# INTRO_Robot_Shield.net
KiCad netlist of a schematic drawn in EAGLE
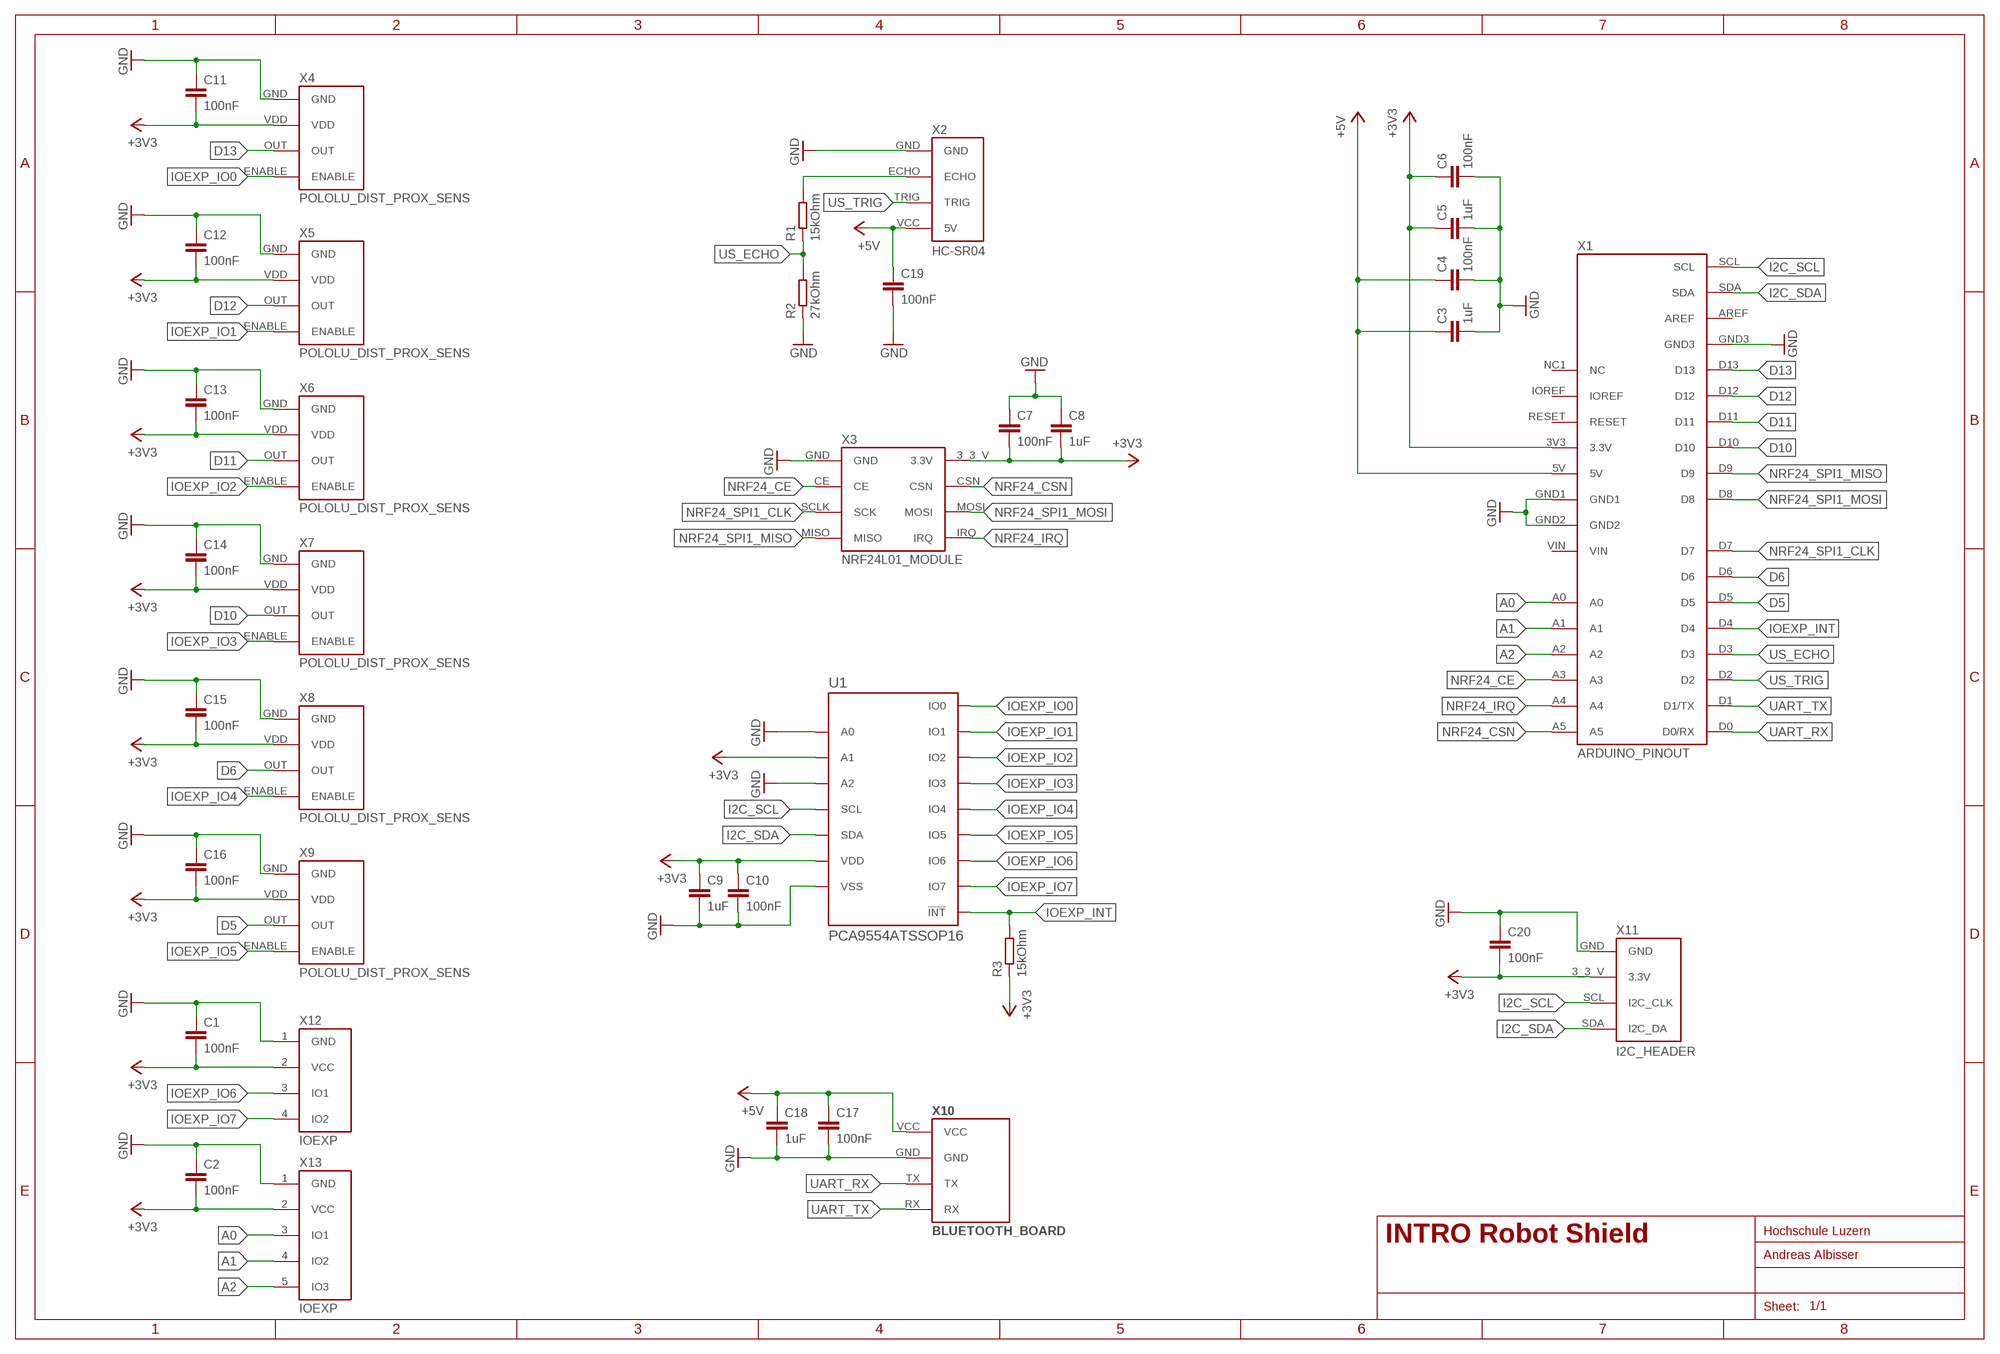
[diagram p0: schematic, sheet 1]

(export (version "E")
  (design (tool "Eeschema 10.0.6"))
  (components
    (comp (ref "C1")
      (value "100nF")
      (footprint "eagle-import:0805")
      (libsource (lib "eagle-import") (part "CAPACITOR0805"))
    )
    (comp (ref "C2")
      (value "100nF")
      (footprint "eagle-import:0805")
      (libsource (lib "eagle-import") (part "CAPACITOR0805"))
    )
    (comp (ref "C3")
      (value "1uF")
      (footprint "eagle-import:0805")
      (libsource (lib "eagle-import") (part "CAPACITOR0805"))
    )
    (comp (ref "C4")
      (value "100nF")
      (footprint "eagle-import:0805")
      (libsource (lib "eagle-import") (part "CAPACITOR0805"))
    )
    (comp (ref "C5")
      (value "1uF")
      (footprint "eagle-import:0805")
      (libsource (lib "eagle-import") (part "CAPACITOR0805"))
    )
    (comp (ref "C6")
      (value "100nF")
      (footprint "eagle-import:0805")
      (libsource (lib "eagle-import") (part "CAPACITOR0805"))
    )
    (comp (ref "C7")
      (value "100nF")
      (footprint "eagle-import:0805")
      (libsource (lib "eagle-import") (part "CAPACITOR0805"))
    )
    (comp (ref "C8")
      (value "1uF")
      (footprint "eagle-import:0805")
      (libsource (lib "eagle-import") (part "CAPACITOR0805"))
    )
    (comp (ref "C9")
      (value "1uF")
      (footprint "eagle-import:0805")
      (libsource (lib "eagle-import") (part "CAPACITOR0805"))
    )
    (comp (ref "C10")
      (value "100nF")
      (footprint "eagle-import:0805")
      (libsource (lib "eagle-import") (part "CAPACITOR0805"))
    )
    (comp (ref "C11")
      (value "100nF")
      (footprint "eagle-import:0805")
      (libsource (lib "eagle-import") (part "CAPACITOR0805"))
    )
    (comp (ref "C12")
      (value "100nF")
      (footprint "eagle-import:0805")
      (libsource (lib "eagle-import") (part "CAPACITOR0805"))
    )
    (comp (ref "C13")
      (value "100nF")
      (footprint "eagle-import:0805")
      (libsource (lib "eagle-import") (part "CAPACITOR0805"))
    )
    (comp (ref "C14")
      (value "100nF")
      (footprint "eagle-import:0805")
      (libsource (lib "eagle-import") (part "CAPACITOR0805"))
    )
    (comp (ref "C15")
      (value "100nF")
      (footprint "eagle-import:0805")
      (libsource (lib "eagle-import") (part "CAPACITOR0805"))
    )
    (comp (ref "C16")
      (value "100nF")
      (footprint "eagle-import:0805")
      (libsource (lib "eagle-import") (part "CAPACITOR0805"))
    )
    (comp (ref "C17")
      (value "100nF")
      (footprint "eagle-import:0805")
      (libsource (lib "eagle-import") (part "CAPACITOR0805"))
    )
    (comp (ref "C18")
      (value "1uF")
      (footprint "eagle-import:0805")
      (libsource (lib "eagle-import") (part "CAPACITOR0805"))
    )
    (comp (ref "C19")
      (value "100nF")
      (footprint "eagle-import:0805")
      (libsource (lib "eagle-import") (part "CAPACITOR0805"))
    )
    (comp (ref "C20")
      (value "100nF")
      (footprint "eagle-import:0805")
      (libsource (lib "eagle-import") (part "CAPACITOR0805"))
    )
    (comp (ref "R1")
      (value "15kOhm")
      (footprint "eagle-import:0805")
      (libsource (lib "eagle-import") (part "RESISTOR0805"))
    )
    (comp (ref "R2")
      (value "27kOhm")
      (footprint "eagle-import:0805")
      (libsource (lib "eagle-import") (part "RESISTOR0805"))
    )
    (comp (ref "R3")
      (value "15kOhm")
      (footprint "eagle-import:0805")
      (libsource (lib "eagle-import") (part "RESISTOR0805"))
    )
    (comp (ref "U1")
      (value "PCA9554ATSSOP16")
      (footprint "eagle-import:TSSOP16")
      (libsource (lib "eagle-import") (part "PCA9554ATSSOP16"))
    )
    (comp (ref "X1")
      (value "ARDUINO_PINOUT")
      (footprint "eagle-import:ARDUINO_PINOUT_INNER_LABEL")
      (libsource (lib "eagle-import") (part "ARDUINO_PINOUTINNER_LABEL"))
    )
    (comp (ref "X2")
      (value "HC-SR04")
      (footprint "eagle-import:HC-SR04_FOOTPRINT")
      (libsource (lib "eagle-import") (part "HC-SR04"))
    )
    (comp (ref "X3")
      (value "NRF24L01_MODULE")
      (footprint "eagle-import:NRF24L01_MODULE_FOOTPRINT")
      (libsource (lib "eagle-import") (part "NRF24L01_MODULE"))
    )
    (comp (ref "X4")
      (value "POLOLU_DIST_PROX_SENS")
      (footprint "eagle-import:POLOLU_DIST_PROX_SENS_FOOTPRINT")
      (libsource (lib "eagle-import") (part "POLOLU_DIST_PROX_SENS"))
    )
    (comp (ref "X5")
      (value "POLOLU_DIST_PROX_SENS")
      (footprint "eagle-import:POLOLU_DIST_PROX_SENS_FOOTPRINT")
      (libsource (lib "eagle-import") (part "POLOLU_DIST_PROX_SENS"))
    )
    (comp (ref "X6")
      (value "POLOLU_DIST_PROX_SENS")
      (footprint "eagle-import:POLOLU_DIST_PROX_SENS_FOOTPRINT")
      (libsource (lib "eagle-import") (part "POLOLU_DIST_PROX_SENS"))
    )
    (comp (ref "X7")
      (value "POLOLU_DIST_PROX_SENS")
      (footprint "eagle-import:POLOLU_DIST_PROX_SENS_FOOTPRINT")
      (libsource (lib "eagle-import") (part "POLOLU_DIST_PROX_SENS"))
    )
    (comp (ref "X8")
      (value "POLOLU_DIST_PROX_SENS")
      (footprint "eagle-import:POLOLU_DIST_PROX_SENS_FOOTPRINT")
      (libsource (lib "eagle-import") (part "POLOLU_DIST_PROX_SENS"))
    )
    (comp (ref "X9")
      (value "POLOLU_DIST_PROX_SENS")
      (footprint "eagle-import:POLOLU_DIST_PROX_SENS_FOOTPRINT")
      (libsource (lib "eagle-import") (part "POLOLU_DIST_PROX_SENS"))
    )
    (comp (ref "X10")
      (value "BLUETOOTH_BOARD")
      (footprint "eagle-import:BT_BOARD_FOOTPRINT")
      (libsource (lib "eagle-import") (part "BLUETOOTH_BOARD"))
    )
    (comp (ref "X11")
      (value "I2C_HEADER")
      (footprint "eagle-import:I2C_HEADER_FOOTPRINT")
      (libsource (lib "eagle-import") (part "I2C_HEADER"))
    )
    (comp (ref "X12")
      (value "IOEXP")
      (footprint "eagle-import:CONNECTORS_STIFTLEISTE_1X4_2.54")
      (libsource (lib "eagle-import") (part "IOEXP_2PTHT_2.54MM"))
    )
    (comp (ref "X13")
      (value "IOEXP")
      (footprint "eagle-import:CONNECTORS_STIFTLEISTE_1X5_2.54")
      (libsource (lib "eagle-import") (part "IOEXP_3PTHT_2.54MM"))
    )
  )
  (nets
    (net (code "1") (name "+3V3") (class "Default")
      (node (ref "C1") (pin "2") (pinfunction "2_2") (pintype "passive"))
      (node (ref "C10") (pin "1") (pinfunction "1_1") (pintype "passive"))
      (node (ref "C11") (pin "2") (pinfunction "2_2") (pintype "passive"))
      (node (ref "C12") (pin "2") (pinfunction "2_2") (pintype "passive"))
      (node (ref "C13") (pin "2") (pinfunction "2_2") (pintype "passive"))
      (node (ref "C14") (pin "2") (pinfunction "2_2") (pintype "passive"))
      (node (ref "C15") (pin "2") (pinfunction "2_2") (pintype "passive"))
      (node (ref "C16") (pin "2") (pinfunction "2_2") (pintype "passive"))
      (node (ref "C2") (pin "2") (pinfunction "2_2") (pintype "passive"))
      (node (ref "C20") (pin "2") (pinfunction "2_2") (pintype "passive"))
      (node (ref "C5") (pin "1") (pinfunction "1_1") (pintype "passive"))
      (node (ref "C6") (pin "1") (pinfunction "1_1") (pintype "passive"))
      (node (ref "C7") (pin "2") (pinfunction "2_2") (pintype "passive"))
      (node (ref "C8") (pin "2") (pinfunction "2_2") (pintype "passive"))
      (node (ref "C9") (pin "1") (pinfunction "1_1") (pintype "passive"))
      (node (ref "R3") (pin "1") (pinfunction "1_1") (pintype "passive"))
      (node (ref "U1") (pin "16") (pinfunction "VDD_16") (pintype "bidirectional"))
      (node (ref "U1") (pin "2") (pinfunction "A1_2") (pintype "bidirectional"))
      (node (ref "X1") (pin "3V3") (pinfunction "3.3V_3V3") (pintype "bidirectional"))
      (node (ref "X11") (pin "3_3_V") (pinfunction "3.3V_3_3_V") (pintype "bidirectional"))
      (node (ref "X12") (pin "2") (pinfunction "VCC_2") (pintype "bidirectional"))
      (node (ref "X13") (pin "2") (pinfunction "VCC_2") (pintype "bidirectional"))
      (node (ref "X3") (pin "3_3_V") (pinfunction "3.3V_3_3_V") (pintype "bidirectional"))
      (node (ref "X4") (pin "VDD") (pinfunction "VDD_VDD") (pintype "bidirectional"))
      (node (ref "X5") (pin "VDD") (pinfunction "VDD_VDD") (pintype "bidirectional"))
      (node (ref "X6") (pin "VDD") (pinfunction "VDD_VDD") (pintype "bidirectional"))
      (node (ref "X7") (pin "VDD") (pinfunction "VDD_VDD") (pintype "bidirectional"))
      (node (ref "X8") (pin "VDD") (pinfunction "VDD_VDD") (pintype "bidirectional"))
      (node (ref "X9") (pin "VDD") (pinfunction "VDD_VDD") (pintype "bidirectional"))
    )
    (net (code "2") (name "+5V") (class "Default")
      (node (ref "C17") (pin "1") (pinfunction "1_1") (pintype "passive"))
      (node (ref "C18") (pin "1") (pinfunction "1_1") (pintype "passive"))
      (node (ref "C19") (pin "1") (pinfunction "1_1") (pintype "passive"))
      (node (ref "C3") (pin "1") (pinfunction "1_1") (pintype "passive"))
      (node (ref "C4") (pin "1") (pinfunction "1_1") (pintype "passive"))
      (node (ref "X1") (pin "5V") (pinfunction "5V_5V") (pintype "bidirectional"))
      (node (ref "X10") (pin "VCC") (pinfunction "VCC_VCC") (pintype "bidirectional"))
      (node (ref "X2") (pin "VCC") (pinfunction "5V_VCC") (pintype "bidirectional"))
    )
    (net (code "3") (name "A0") (class "Default")
      (node (ref "X1") (pin "A0") (pinfunction "A0_A0") (pintype "bidirectional"))
      (node (ref "X13") (pin "3") (pinfunction "IO1_3") (pintype "bidirectional"))
    )
    (net (code "4") (name "A1") (class "Default")
      (node (ref "X1") (pin "A1") (pinfunction "A1_A1") (pintype "bidirectional"))
      (node (ref "X13") (pin "4") (pinfunction "IO2_4") (pintype "bidirectional"))
    )
    (net (code "5") (name "A2") (class "Default")
      (node (ref "X1") (pin "A2") (pinfunction "A2_A2") (pintype "bidirectional"))
      (node (ref "X13") (pin "5") (pinfunction "IO3_5") (pintype "bidirectional"))
    )
    (net (code "6") (name "D5") (class "Default")
      (node (ref "X1") (pin "D5") (pinfunction "D5_D5") (pintype "bidirectional"))
      (node (ref "X9") (pin "OUT") (pinfunction "OUT_OUT") (pintype "bidirectional"))
    )
    (net (code "7") (name "D6") (class "Default")
      (node (ref "X1") (pin "D6") (pinfunction "D6_D6") (pintype "bidirectional"))
      (node (ref "X8") (pin "OUT") (pinfunction "OUT_OUT") (pintype "bidirectional"))
    )
    (net (code "8") (name "D10") (class "Default")
      (node (ref "X1") (pin "D10") (pinfunction "D10_D10") (pintype "bidirectional"))
      (node (ref "X7") (pin "OUT") (pinfunction "OUT_OUT") (pintype "bidirectional"))
    )
    (net (code "9") (name "D11") (class "Default")
      (node (ref "X1") (pin "D11") (pinfunction "D11_D11") (pintype "bidirectional"))
      (node (ref "X6") (pin "OUT") (pinfunction "OUT_OUT") (pintype "bidirectional"))
    )
    (net (code "10") (name "D12") (class "Default")
      (node (ref "X1") (pin "D12") (pinfunction "D12_D12") (pintype "bidirectional"))
      (node (ref "X5") (pin "OUT") (pinfunction "OUT_OUT") (pintype "bidirectional"))
    )
    (net (code "11") (name "D13") (class "Default")
      (node (ref "X1") (pin "D13") (pinfunction "D13_D13") (pintype "bidirectional"))
      (node (ref "X4") (pin "OUT") (pinfunction "OUT_OUT") (pintype "bidirectional"))
    )
    (net (code "12") (name "GND") (class "Default")
      (node (ref "C1") (pin "1") (pinfunction "1_1") (pintype "passive"))
      (node (ref "C10") (pin "2") (pinfunction "2_2") (pintype "passive"))
      (node (ref "C11") (pin "1") (pinfunction "1_1") (pintype "passive"))
      (node (ref "C12") (pin "1") (pinfunction "1_1") (pintype "passive"))
      (node (ref "C13") (pin "1") (pinfunction "1_1") (pintype "passive"))
      (node (ref "C14") (pin "1") (pinfunction "1_1") (pintype "passive"))
      (node (ref "C15") (pin "1") (pinfunction "1_1") (pintype "passive"))
      (node (ref "C16") (pin "1") (pinfunction "1_1") (pintype "passive"))
      (node (ref "C17") (pin "2") (pinfunction "2_2") (pintype "passive"))
      (node (ref "C18") (pin "2") (pinfunction "2_2") (pintype "passive"))
      (node (ref "C19") (pin "2") (pinfunction "2_2") (pintype "passive"))
      (node (ref "C2") (pin "1") (pinfunction "1_1") (pintype "passive"))
      (node (ref "C20") (pin "1") (pinfunction "1_1") (pintype "passive"))
      (node (ref "C3") (pin "2") (pinfunction "2_2") (pintype "passive"))
      (node (ref "C4") (pin "2") (pinfunction "2_2") (pintype "passive"))
      (node (ref "C5") (pin "2") (pinfunction "2_2") (pintype "passive"))
      (node (ref "C6") (pin "2") (pinfunction "2_2") (pintype "passive"))
      (node (ref "C7") (pin "1") (pinfunction "1_1") (pintype "passive"))
      (node (ref "C8") (pin "1") (pinfunction "1_1") (pintype "passive"))
      (node (ref "C9") (pin "2") (pinfunction "2_2") (pintype "passive"))
      (node (ref "R2") (pin "1") (pinfunction "1_1") (pintype "passive"))
      (node (ref "U1") (pin "1") (pinfunction "A0_1") (pintype "bidirectional"))
      (node (ref "U1") (pin "3") (pinfunction "A2_3") (pintype "bidirectional"))
      (node (ref "U1") (pin "8") (pinfunction "VSS_8") (pintype "bidirectional"))
      (node (ref "X1") (pin "GND1") (pinfunction "GND1_GND1") (pintype "bidirectional"))
      (node (ref "X1") (pin "GND2") (pinfunction "GND2_GND2") (pintype "bidirectional"))
      (node (ref "X1") (pin "GND3") (pinfunction "GND3_GND3") (pintype "bidirectional"))
      (node (ref "X10") (pin "GND") (pinfunction "GND_GND") (pintype "bidirectional"))
      (node (ref "X11") (pin "GND") (pinfunction "GND_GND") (pintype "bidirectional"))
      (node (ref "X12") (pin "1") (pinfunction "GND_1") (pintype "bidirectional"))
      (node (ref "X13") (pin "1") (pinfunction "GND_1") (pintype "bidirectional"))
      (node (ref "X2") (pin "GND") (pinfunction "GND_GND") (pintype "bidirectional"))
      (node (ref "X3") (pin "GND") (pinfunction "GND_GND") (pintype "bidirectional"))
      (node (ref "X4") (pin "GND") (pinfunction "GND_GND") (pintype "bidirectional"))
      (node (ref "X5") (pin "GND") (pinfunction "GND_GND") (pintype "bidirectional"))
      (node (ref "X6") (pin "GND") (pinfunction "GND_GND") (pintype "bidirectional"))
      (node (ref "X7") (pin "GND") (pinfunction "GND_GND") (pintype "bidirectional"))
      (node (ref "X8") (pin "GND") (pinfunction "GND_GND") (pintype "bidirectional"))
      (node (ref "X9") (pin "GND") (pinfunction "GND_GND") (pintype "bidirectional"))
    )
    (net (code "13") (name "I2C_SCL") (class "Default")
      (node (ref "U1") (pin "14") (pinfunction "SCL_14") (pintype "bidirectional"))
      (node (ref "X1") (pin "SCL") (pinfunction "SCL_SCL") (pintype "bidirectional"))
      (node (ref "X11") (pin "SCL") (pinfunction "I2C_CLK_SCL") (pintype "bidirectional"))
    )
    (net (code "14") (name "I2C_SDA") (class "Default")
      (node (ref "U1") (pin "15") (pinfunction "SDA_15") (pintype "bidirectional"))
      (node (ref "X1") (pin "SDA") (pinfunction "SDA_SDA") (pintype "bidirectional"))
      (node (ref "X11") (pin "SDA") (pinfunction "I2C_DA_SDA") (pintype "bidirectional"))
    )
    (net (code "15") (name "IOEXP_INT") (class "Default")
      (node (ref "R3") (pin "2") (pinfunction "2_2") (pintype "passive"))
      (node (ref "U1") (pin "13") (pinfunction "~{INT}_13") (pintype "bidirectional"))
      (node (ref "X1") (pin "D4") (pinfunction "D4_D4") (pintype "bidirectional"))
    )
    (net (code "16") (name "IOEXP_IO0") (class "Default")
      (node (ref "U1") (pin "4") (pinfunction "IO0_4") (pintype "bidirectional"))
      (node (ref "X4") (pin "ENABLE") (pinfunction "ENABLE_ENABLE") (pintype "bidirectional"))
    )
    (net (code "17") (name "IOEXP_IO1") (class "Default")
      (node (ref "U1") (pin "5") (pinfunction "IO1_5") (pintype "bidirectional"))
      (node (ref "X5") (pin "ENABLE") (pinfunction "ENABLE_ENABLE") (pintype "bidirectional"))
    )
    (net (code "18") (name "IOEXP_IO2") (class "Default")
      (node (ref "U1") (pin "6") (pinfunction "IO2_6") (pintype "bidirectional"))
      (node (ref "X6") (pin "ENABLE") (pinfunction "ENABLE_ENABLE") (pintype "bidirectional"))
    )
    (net (code "19") (name "IOEXP_IO3") (class "Default")
      (node (ref "U1") (pin "7") (pinfunction "IO3_7") (pintype "bidirectional"))
      (node (ref "X7") (pin "ENABLE") (pinfunction "ENABLE_ENABLE") (pintype "bidirectional"))
    )
    (net (code "20") (name "IOEXP_IO4") (class "Default")
      (node (ref "U1") (pin "9") (pinfunction "IO4_9") (pintype "bidirectional"))
      (node (ref "X8") (pin "ENABLE") (pinfunction "ENABLE_ENABLE") (pintype "bidirectional"))
    )
    (net (code "21") (name "IOEXP_IO5") (class "Default")
      (node (ref "U1") (pin "10") (pinfunction "IO5_10") (pintype "bidirectional"))
      (node (ref "X9") (pin "ENABLE") (pinfunction "ENABLE_ENABLE") (pintype "bidirectional"))
    )
    (net (code "22") (name "IOEXP_IO6") (class "Default")
      (node (ref "U1") (pin "11") (pinfunction "IO6_11") (pintype "bidirectional"))
      (node (ref "X12") (pin "3") (pinfunction "IO1_3") (pintype "bidirectional"))
    )
    (net (code "23") (name "IOEXP_IO7") (class "Default")
      (node (ref "U1") (pin "12") (pinfunction "IO7_12") (pintype "bidirectional"))
      (node (ref "X12") (pin "4") (pinfunction "IO2_4") (pintype "bidirectional"))
    )
    (net (code "24") (name "NRF24_CE") (class "Default")
      (node (ref "X1") (pin "A3") (pinfunction "A3_A3") (pintype "bidirectional"))
      (node (ref "X3") (pin "CE") (pinfunction "CE_CE") (pintype "bidirectional"))
    )
    (net (code "25") (name "NRF24_CSN") (class "Default")
      (node (ref "X1") (pin "A5") (pinfunction "A5_A5") (pintype "bidirectional"))
      (node (ref "X3") (pin "CSN") (pinfunction "CSN_CSN") (pintype "bidirectional"))
    )
    (net (code "26") (name "NRF24_IRQ") (class "Default")
      (node (ref "X1") (pin "A4") (pinfunction "A4_A4") (pintype "bidirectional"))
      (node (ref "X3") (pin "IRQ") (pinfunction "IRQ_IRQ") (pintype "bidirectional"))
    )
    (net (code "27") (name "NRF24_SPI1_CLK") (class "Default")
      (node (ref "X1") (pin "D7") (pinfunction "D7_D7") (pintype "bidirectional"))
      (node (ref "X3") (pin "SCLK") (pinfunction "SCK_SCLK") (pintype "bidirectional"))
    )
    (net (code "28") (name "NRF24_SPI1_MISO") (class "Default")
      (node (ref "X1") (pin "D9") (pinfunction "D9_D9") (pintype "bidirectional"))
      (node (ref "X3") (pin "MISO") (pinfunction "MISO_MISO") (pintype "bidirectional"))
    )
    (net (code "29") (name "NRF24_SPI1_MOSI") (class "Default")
      (node (ref "X1") (pin "D8") (pinfunction "D8_D8") (pintype "bidirectional"))
      (node (ref "X3") (pin "MOSI") (pinfunction "MOSI_MOSI") (pintype "bidirectional"))
    )
    (net (code "30") (name "Net-(R1-Pad2)") (class "Default")
      (node (ref "R1") (pin "2") (pinfunction "2_2") (pintype "passive"))
      (node (ref "X2") (pin "ECHO") (pinfunction "ECHO_ECHO") (pintype "bidirectional"))
    )
    (net (code "31") (name "UART_RX") (class "Default")
      (node (ref "X1") (pin "D0") (pinfunction "D0/RX_D0") (pintype "bidirectional"))
      (node (ref "X10") (pin "TX") (pinfunction "TX_TX") (pintype "bidirectional"))
    )
    (net (code "32") (name "UART_TX") (class "Default")
      (node (ref "X1") (pin "D1") (pinfunction "D1/TX_D1") (pintype "bidirectional"))
      (node (ref "X10") (pin "RX") (pinfunction "RX_RX") (pintype "bidirectional"))
    )
    (net (code "33") (name "US_ECHO") (class "Default")
      (node (ref "R1") (pin "1") (pinfunction "1_1") (pintype "passive"))
      (node (ref "R2") (pin "2") (pinfunction "2_2") (pintype "passive"))
      (node (ref "X1") (pin "D3") (pinfunction "D3_D3") (pintype "bidirectional"))
    )
    (net (code "34") (name "US_TRIG") (class "Default")
      (node (ref "X1") (pin "D2") (pinfunction "D2_D2") (pintype "bidirectional"))
      (node (ref "X2") (pin "TRIG") (pinfunction "TRIG_TRIG") (pintype "bidirectional"))
    )
    (net (code "35") (name "unconnected-(X1-NC-PadNC1)") (class "Default")
      (node (ref "X1") (pin "NC1") (pinfunction "NC_NC1") (pintype "bidirectional"))
    )
    (net (code "36") (name "unconnected-(X1-PadAREF)") (class "Default")
      (node (ref "X1") (pin "AREF") (pinfunction "AREF_AREF") (pintype "bidirectional"))
    )
    (net (code "37") (name "unconnected-(X1-PadIOREF)") (class "Default")
      (node (ref "X1") (pin "IOREF") (pinfunction "IOREF_IOREF") (pintype "bidirectional"))
    )
    (net (code "38") (name "unconnected-(X1-PadRESET)") (class "Default")
      (node (ref "X1") (pin "RESET") (pinfunction "RESET_RESET") (pintype "bidirectional"))
    )
    (net (code "39") (name "unconnected-(X1-PadVIN)") (class "Default")
      (node (ref "X1") (pin "VIN") (pinfunction "VIN_VIN") (pintype "bidirectional"))
    )
  )
)
